# Variable_Load.net
KiCad netlist of a schematic drawn in EAGLE
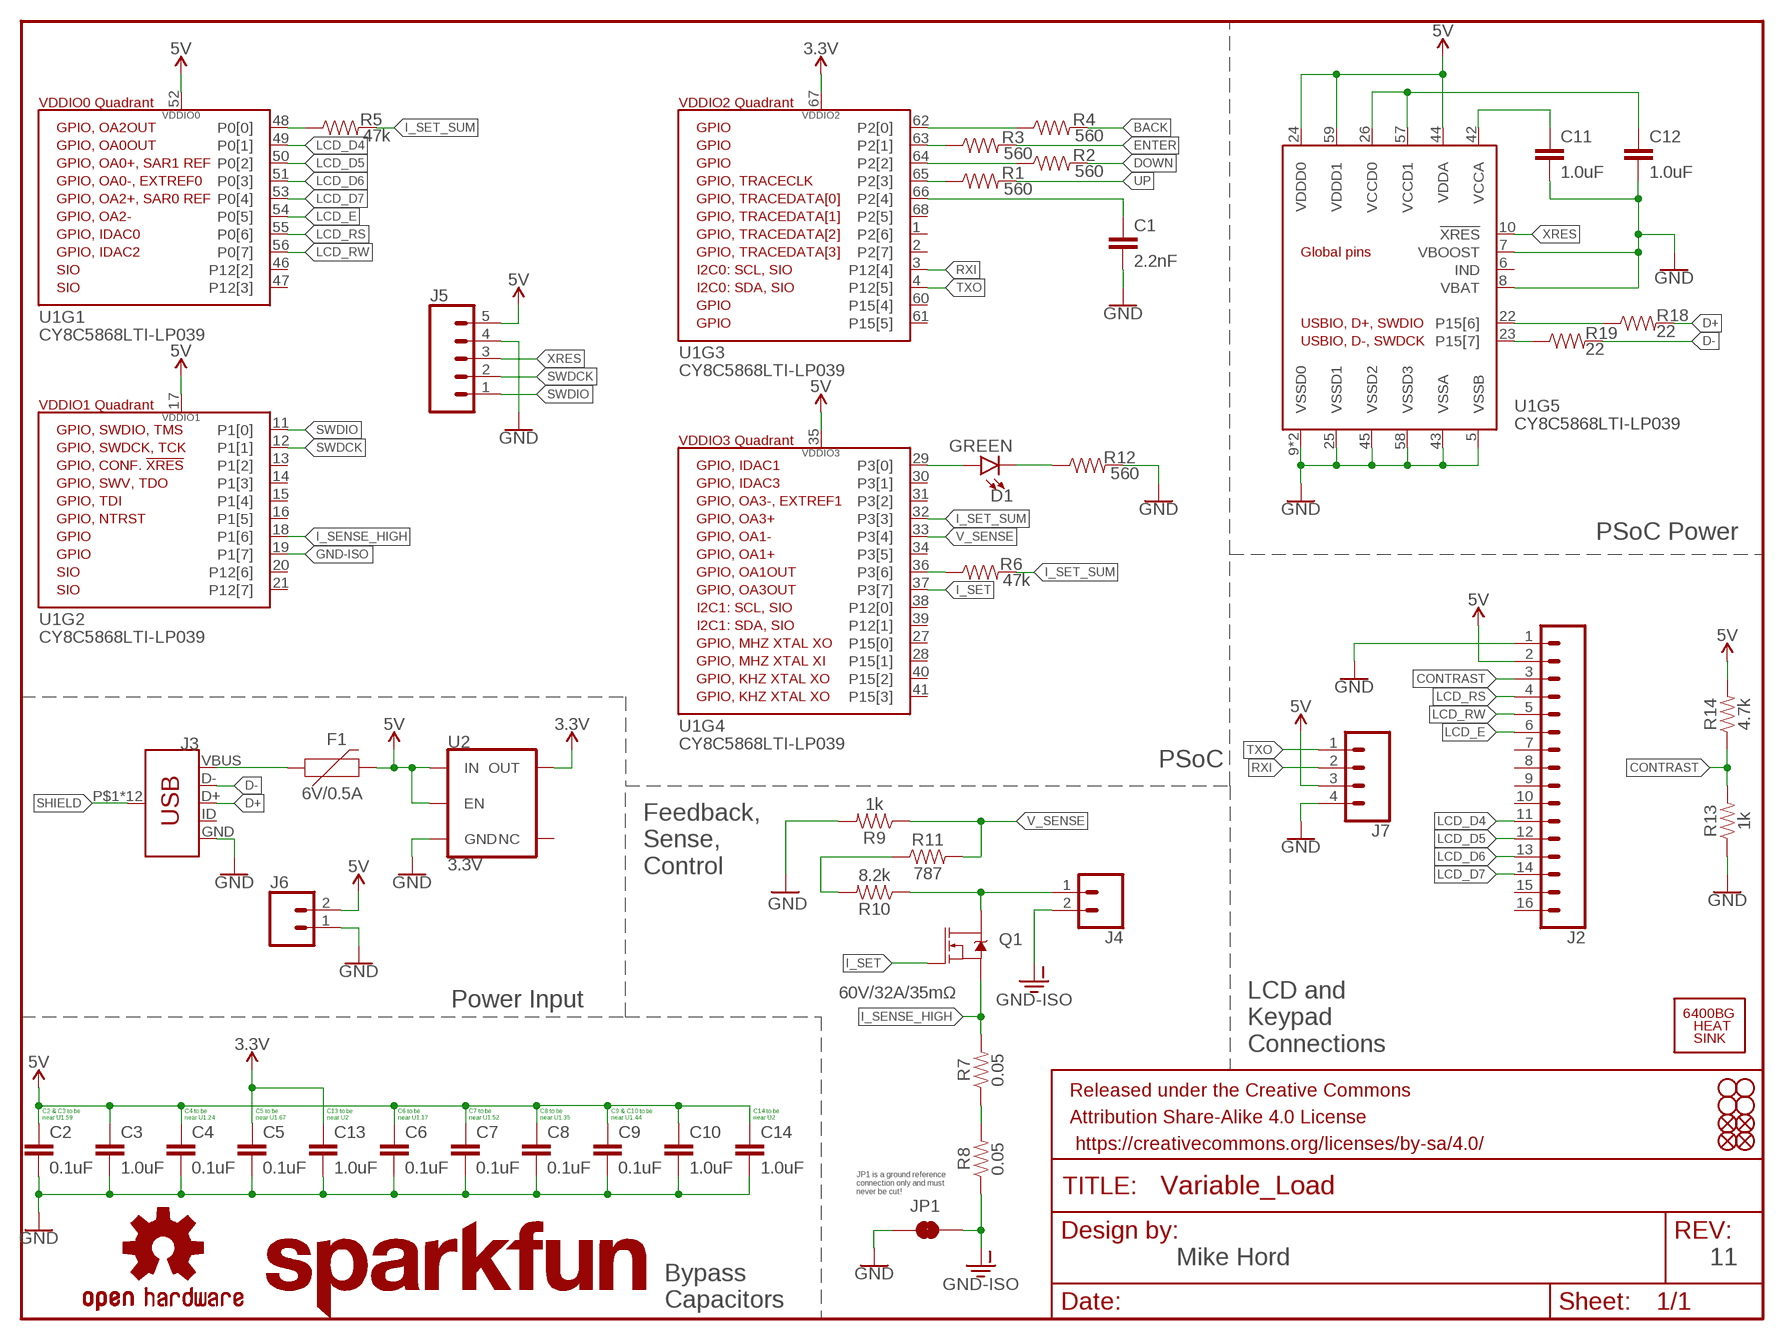
[diagram p0: schematic, sheet 1]

(export (version "E")
  (design (tool "Eeschema 10.0.6"))
  (components
    (comp (ref "C1")
      (value "2.2nF")
      (footprint "eagle-import:0603")
      (libsource (lib "eagle-import") (part "2.2NF/2200PF-0603-50V-10%"))
    )
    (comp (ref "C2")
      (value "0.1uF")
      (footprint "eagle-import:0402")
      (libsource (lib "eagle-import") (part "0.1UF-0402-16V-10%"))
    )
    (comp (ref "C3")
      (value "1.0uF")
      (footprint "eagle-import:0402")
      (libsource (lib "eagle-import") (part "1.0UF-0402-16V-10%"))
    )
    (comp (ref "C4")
      (value "0.1uF")
      (footprint "eagle-import:0402")
      (libsource (lib "eagle-import") (part "0.1UF-0402-16V-10%"))
    )
    (comp (ref "C5")
      (value "0.1uF")
      (footprint "eagle-import:0402")
      (libsource (lib "eagle-import") (part "0.1UF-0402-16V-10%"))
    )
    (comp (ref "C6")
      (value "0.1uF")
      (footprint "eagle-import:0402")
      (libsource (lib "eagle-import") (part "0.1UF-0402-16V-10%"))
    )
    (comp (ref "C7")
      (value "0.1uF")
      (footprint "eagle-import:0402")
      (libsource (lib "eagle-import") (part "0.1UF-0402-16V-10%"))
    )
    (comp (ref "C8")
      (value "0.1uF")
      (footprint "eagle-import:0402")
      (libsource (lib "eagle-import") (part "0.1UF-0402-16V-10%"))
    )
    (comp (ref "C9")
      (value "0.1uF")
      (footprint "eagle-import:0402")
      (libsource (lib "eagle-import") (part "0.1UF-0402-16V-10%"))
    )
    (comp (ref "C10")
      (value "1.0uF")
      (footprint "eagle-import:0402")
      (libsource (lib "eagle-import") (part "1.0UF-0402-16V-10%"))
    )
    (comp (ref "C11")
      (value "1.0uF")
      (footprint "eagle-import:0402")
      (libsource (lib "eagle-import") (part "1.0UF-0402-16V-10%"))
    )
    (comp (ref "C12")
      (value "1.0uF")
      (footprint "eagle-import:0402")
      (libsource (lib "eagle-import") (part "1.0UF-0402-16V-10%"))
    )
    (comp (ref "C13")
      (value "1.0uF")
      (footprint "eagle-import:0402")
      (libsource (lib "eagle-import") (part "1.0UF-0402-16V-10%"))
    )
    (comp (ref "C14")
      (value "1.0uF")
      (footprint "eagle-import:0402")
      (libsource (lib "eagle-import") (part "1.0UF-0402-16V-10%"))
    )
    (comp (ref "D1")
      (value "GREEN")
      (footprint "eagle-import:LED-1206-BOTTOM")
      (libsource (lib "eagle-import") (part "LED1206-BOTTOM"))
    )
    (comp (ref "F1")
      (value "6V/0.5A")
      (footprint "eagle-import:1206")
      (libsource (lib "eagle-import") (part "PPTC_HALF-AMP"))
    )
    (comp (ref "FD1")
      (value "FIDUCIAL1X2")
      (footprint "eagle-import:FIDUCIAL-1X2")
      (libsource (lib "eagle-import") (part "FIDUCIAL1X2"))
    )
    (comp (ref "FD2")
      (value "FIDUCIAL1X2")
      (footprint "eagle-import:FIDUCIAL-1X2")
      (libsource (lib "eagle-import") (part "FIDUCIAL1X2"))
    )
    (comp (ref "FD3")
      (value "FIDUCIAL1X2")
      (footprint "eagle-import:FIDUCIAL-1X2")
      (libsource (lib "eagle-import") (part "FIDUCIAL1X2"))
    )
    (comp (ref "FD4")
      (value "FIDUCIAL1X2")
      (footprint "eagle-import:FIDUCIAL-1X2")
      (libsource (lib "eagle-import") (part "FIDUCIAL1X2"))
    )
    (comp (ref "FRAME1")
      (value "FRAME-LETTER")
      (footprint "eagle-import:CREATIVE_COMMONS")
      (libsource (lib "eagle-import") (part "FRAME-LETTER"))
    )
    (comp (ref "H1")
      (value "6400BG_HEATSINK")
      (footprint "eagle-import:6400BG_HEATSINK")
      (libsource (lib "eagle-import") (part "6400BG_HEATSINK"))
    )
    (comp (ref "H2")
      (value "STAND-OFF")
      (footprint "eagle-import:STAND-OFF")
      (libsource (lib "eagle-import") (part "STAND-OFF"))
    )
    (comp (ref "H3")
      (value "STAND-OFF")
      (footprint "eagle-import:STAND-OFF")
      (libsource (lib "eagle-import") (part "STAND-OFF"))
    )
    (comp (ref "H4")
      (value "STAND-OFF")
      (footprint "eagle-import:STAND-OFF")
      (libsource (lib "eagle-import") (part "STAND-OFF"))
    )
    (comp (ref "H5")
      (value "STAND-OFF")
      (footprint "eagle-import:STAND-OFF")
      (libsource (lib "eagle-import") (part "STAND-OFF"))
    )
    (comp (ref "J2")
      (value "CONN_16")
      (footprint "eagle-import:1X16")
      (libsource (lib "eagle-import") (part "CONN_16"))
    )
    (comp (ref "J3")
      (value "AMP FCI 10103594-0001LF")
      (footprint "eagle-import:USB-MICROB-PTH")
      (libsource (lib "eagle-import") (part "USB_MICRO-B_HALF_PTH"))
    )
    (comp (ref "J4")
      (value "CONN_023.5MM_LOCK")
      (footprint "eagle-import:SCREWTERMINAL-3.5MM-2_LOCK")
      (libsource (lib "eagle-import") (part "CONN_023.5MM_LOCK"))
    )
    (comp (ref "J5")
      (value "CONN_05")
      (footprint "eagle-import:1X05")
      (libsource (lib "eagle-import") (part "CONN_05"))
    )
    (comp (ref "J6")
      (value "CONN_02")
      (footprint "eagle-import:1X02")
      (libsource (lib "eagle-import") (part "CONN_02"))
    )
    (comp (ref "J7")
      (value "CONN_04")
      (footprint "eagle-import:1X04")
      (libsource (lib "eagle-import") (part "CONN_04"))
    )
    (comp (ref "JP1")
      (value "JUMPER-SMT_2_NC_TRACE_NO-SILK")
      (footprint "eagle-import:SMT-JUMPER_2_NC_TRACE_NO-SILK")
      (libsource (lib "eagle-import") (part "JUMPER-SMT_2_NC_TRACE_NO-SILK"))
    )
    (comp (ref "LOGO1")
      (value "OSHW-LOGOM")
      (footprint "eagle-import:OSHW-LOGO-M")
      (libsource (lib "eagle-import") (part "OSHW-LOGOM"))
    )
    (comp (ref "LOGO2")
      (value "SFE_LOGO_NAME.3_INCH")
      (footprint "eagle-import:SFE_LOGO_NAME_.3")
      (libsource (lib "eagle-import") (part "SFE_LOGO_NAME.3_INCH"))
    )
    (comp (ref "LOGO3")
      (value "SFE_LOGO_NAME.3_INCH")
      (footprint "eagle-import:SFE_LOGO_NAME_.3")
      (libsource (lib "eagle-import") (part "SFE_LOGO_NAME.3_INCH"))
    )
    (comp (ref "Q1")
      (value "60V/32A/35mΩ")
      (footprint "eagle-import:TO220V")
      (libsource (lib "eagle-import") (part "MOSFET-NCH-FQP30N06L"))
    )
    (comp (ref "R1")
      (value "560")
      (footprint "eagle-import:0402")
      (libsource (lib "eagle-import") (part "560OHM_0402_1%"))
    )
    (comp (ref "R2")
      (value "560")
      (footprint "eagle-import:0402")
      (libsource (lib "eagle-import") (part "560OHM_0402_1%"))
    )
    (comp (ref "R3")
      (value "560")
      (footprint "eagle-import:0402")
      (libsource (lib "eagle-import") (part "560OHM_0402_1%"))
    )
    (comp (ref "R4")
      (value "560")
      (footprint "eagle-import:0402")
      (libsource (lib "eagle-import") (part "560OHM_0402_1%"))
    )
    (comp (ref "R5")
      (value "47k")
      (footprint "eagle-import:0603")
      (libsource (lib "eagle-import") (part "47KOHM-0603-1/10W-1%"))
    )
    (comp (ref "R6")
      (value "47k")
      (footprint "eagle-import:0603")
      (libsource (lib "eagle-import") (part "47KOHM-0603-1/10W-1%"))
    )
    (comp (ref "R7")
      (value "0.05")
      (footprint "eagle-import:2512")
      (libsource (lib "eagle-import") (part "0.05OHM-2512-3W-1%"))
    )
    (comp (ref "R8")
      (value "0.05")
      (footprint "eagle-import:2512")
      (libsource (lib "eagle-import") (part "0.05OHM-2512-3W-1%"))
    )
    (comp (ref "R9")
      (value "1k")
      (footprint "eagle-import:0603")
      (libsource (lib "eagle-import") (part "1KOHM-0603-1/10W-1%"))
    )
    (comp (ref "R10")
      (value "8.2k")
      (footprint "eagle-import:0603")
      (libsource (lib "eagle-import") (part "8.2KOHM-0603-1/10W-5%"))
    )
    (comp (ref "R11")
      (value "787")
      (footprint "eagle-import:0603")
      (libsource (lib "eagle-import") (part "787OHM-0603-1/10W-1%"))
    )
    (comp (ref "R12")
      (value "560")
      (footprint "eagle-import:0402")
      (libsource (lib "eagle-import") (part "560OHM_0402_1%"))
    )
    (comp (ref "R13")
      (value "1k")
      (footprint "eagle-import:0603")
      (libsource (lib "eagle-import") (part "1KOHM-0603-1/10W-1%"))
    )
    (comp (ref "R14")
      (value "4.7k")
      (footprint "eagle-import:0603")
      (libsource (lib "eagle-import") (part "4.7KOHM-0603-1/10W-1%"))
    )
    (comp (ref "R18")
      (value "22")
      (footprint "eagle-import:0402-RES")
      (libsource (lib "eagle-import") (part "22OHM1/10W1%(0402)"))
    )
    (comp (ref "R19")
      (value "22")
      (footprint "eagle-import:0402-RES")
      (libsource (lib "eagle-import") (part "22OHM1/10W1%(0402)"))
    )
    (comp (ref "U1")
      (value "CY8C5868LTI-LP039")
      (footprint "eagle-import:QFN-68")
      (libsource (lib "eagle-import") (part "PSOC_5LP_68QFN"))
    )
    (comp (ref "U2")
      (value "3.3V")
      (footprint "eagle-import:SOT23-5")
      (libsource (lib "eagle-import") (part "V_REG_AP2112K-3.3V"))
    )
  )
  (nets
    (net (code "1") (name "3.3V") (class "Default")
      (node (ref "C13") (pin "1") (pinfunction "1_1") (pintype "passive"))
      (node (ref "C5") (pin "1") (pinfunction "1_1") (pintype "passive"))
      (node (ref "U1") (pin "67") (pinfunction "VDDIO2_67") (pintype "bidirectional"))
      (node (ref "U2") (pin "5") (pinfunction "OUT_5") (pintype "passive"))
    )
    (net (code "2") (name "5V") (class "Default")
      (node (ref "C10") (pin "1") (pinfunction "1_1") (pintype "passive"))
      (node (ref "C14") (pin "1") (pinfunction "1_1") (pintype "passive"))
      (node (ref "C2") (pin "1") (pinfunction "1_1") (pintype "passive"))
      (node (ref "C3") (pin "1") (pinfunction "1_1") (pintype "passive"))
      (node (ref "C4") (pin "1") (pinfunction "1_1") (pintype "passive"))
      (node (ref "C6") (pin "1") (pinfunction "1_1") (pintype "passive"))
      (node (ref "C7") (pin "1") (pinfunction "1_1") (pintype "passive"))
      (node (ref "C8") (pin "1") (pinfunction "1_1") (pintype "passive"))
      (node (ref "C9") (pin "1") (pinfunction "1_1") (pintype "passive"))
      (node (ref "F1") (pin "2") (pinfunction "2_2") (pintype "bidirectional"))
      (node (ref "J2") (pin "2") (pinfunction "2_2") (pintype "passive"))
      (node (ref "J5") (pin "5") (pinfunction "5_5") (pintype "passive"))
      (node (ref "J6") (pin "2") (pinfunction "2_2") (pintype "passive"))
      (node (ref "J7") (pin "3") (pinfunction "3_3") (pintype "passive"))
      (node (ref "R14") (pin "2") (pinfunction "2_2") (pintype "passive"))
      (node (ref "U1") (pin "17") (pinfunction "VDDIO1_17") (pintype "bidirectional"))
      (node (ref "U1") (pin "24") (pinfunction "VDDD0_24") (pintype "bidirectional"))
      (node (ref "U1") (pin "35") (pinfunction "VDDIO3_35") (pintype "bidirectional"))
      (node (ref "U1") (pin "44") (pinfunction "VDDA_44") (pintype "bidirectional"))
      (node (ref "U1") (pin "52") (pinfunction "VDDIO0_52") (pintype "bidirectional"))
      (node (ref "U1") (pin "59") (pinfunction "VDDD1_59") (pintype "bidirectional"))
      (node (ref "U2") (pin "1") (pinfunction "IN_1") (pintype "input"))
      (node (ref "U2") (pin "3") (pinfunction "EN_3") (pintype "input"))
    )
    (net (code "3") (name "BACK") (class "Default")
      (node (ref "R4") (pin "2") (pinfunction "2_2") (pintype "passive"))
    )
    (net (code "4") (name "CONTRAST") (class "Default")
      (node (ref "J2") (pin "3") (pinfunction "3_3") (pintype "passive"))
      (node (ref "R13") (pin "2") (pinfunction "2_2") (pintype "passive"))
      (node (ref "R14") (pin "1") (pinfunction "1_1") (pintype "passive"))
    )
    (net (code "5") (name "D+") (class "Default")
      (node (ref "J3") (pin "D+") (pinfunction "D+_D+") (pintype "bidirectional"))
      (node (ref "R18") (pin "2") (pinfunction "2_2") (pintype "passive"))
    )
    (net (code "6") (name "D-") (class "Default")
      (node (ref "J3") (pin "D-") (pinfunction "D-_D-") (pintype "bidirectional"))
      (node (ref "R19") (pin "2") (pinfunction "2_2") (pintype "passive"))
    )
    (net (code "7") (name "DOWN") (class "Default")
      (node (ref "R2") (pin "2") (pinfunction "2_2") (pintype "passive"))
    )
    (net (code "8") (name "ENTER") (class "Default")
      (node (ref "R3") (pin "2") (pinfunction "2_2") (pintype "passive"))
    )
    (net (code "9") (name "GND") (class "Default")
      (node (ref "C1") (pin "2") (pinfunction "2_2") (pintype "passive"))
      (node (ref "C10") (pin "2") (pinfunction "2_2") (pintype "passive"))
      (node (ref "C11") (pin "2") (pinfunction "2_2") (pintype "passive"))
      (node (ref "C12") (pin "2") (pinfunction "2_2") (pintype "passive"))
      (node (ref "C13") (pin "2") (pinfunction "2_2") (pintype "passive"))
      (node (ref "C14") (pin "2") (pinfunction "2_2") (pintype "passive"))
      (node (ref "C2") (pin "2") (pinfunction "2_2") (pintype "passive"))
      (node (ref "C3") (pin "2") (pinfunction "2_2") (pintype "passive"))
      (node (ref "C4") (pin "2") (pinfunction "2_2") (pintype "passive"))
      (node (ref "C5") (pin "2") (pinfunction "2_2") (pintype "passive"))
      (node (ref "C6") (pin "2") (pinfunction "2_2") (pintype "passive"))
      (node (ref "C7") (pin "2") (pinfunction "2_2") (pintype "passive"))
      (node (ref "C8") (pin "2") (pinfunction "2_2") (pintype "passive"))
      (node (ref "C9") (pin "2") (pinfunction "2_2") (pintype "passive"))
      (node (ref "J2") (pin "1") (pinfunction "1_1") (pintype "passive"))
      (node (ref "J3") (pin "GND") (pinfunction "GND_GND") (pintype "power_in"))
      (node (ref "J5") (pin "4") (pinfunction "4_4") (pintype "passive"))
      (node (ref "J6") (pin "1") (pinfunction "1_1") (pintype "passive"))
      (node (ref "J7") (pin "4") (pinfunction "4_4") (pintype "passive"))
      (node (ref "JP1") (pin "1") (pinfunction "1_1") (pintype "passive"))
      (node (ref "R12") (pin "2") (pinfunction "2_2") (pintype "passive"))
      (node (ref "R13") (pin "1") (pinfunction "1_1") (pintype "passive"))
      (node (ref "R9") (pin "2") (pinfunction "2_2") (pintype "passive"))
      (node (ref "U1") (pin "25") (pinfunction "VSSD1_25") (pintype "bidirectional"))
      (node (ref "U1") (pin "43") (pinfunction "VSSA_43") (pintype "bidirectional"))
      (node (ref "U1") (pin "45") (pinfunction "VSSD2_45") (pintype "bidirectional"))
      (node (ref "U1") (pin "5") (pinfunction "VSSB_5") (pintype "bidirectional"))
      (node (ref "U1") (pin "58") (pinfunction "VSSD3_58") (pintype "bidirectional"))
      (node (ref "U1") (pin "69") (pinfunction "VSSD0_69") (pintype "bidirectional"))
      (node (ref "U1") (pin "7") (pinfunction "VBOOST_7") (pintype "bidirectional"))
      (node (ref "U1") (pin "8") (pinfunction "VBAT_8") (pintype "bidirectional"))
      (node (ref "U1") (pin "9") (pinfunction "VSSD0_9") (pintype "bidirectional"))
      (node (ref "U2") (pin "2") (pinfunction "GND_2") (pintype "input"))
    )
    (net (code "10") (name "GND-ISO") (class "Default")
      (node (ref "J4") (pin "2") (pinfunction "2_2") (pintype "passive"))
      (node (ref "JP1") (pin "2") (pinfunction "2_2") (pintype "passive"))
      (node (ref "R8") (pin "P$1") (pinfunction "1_P$1") (pintype "passive"))
      (node (ref "U1") (pin "19") (pinfunction "P1[7]_19") (pintype "bidirectional"))
    )
    (net (code "11") (name "I_SENSE_HIGH") (class "Default")
      (node (ref "Q1") (pin "3") (pinfunction "S_3") (pintype "bidirectional"))
      (node (ref "R7") (pin "P$2") (pinfunction "2_P$2") (pintype "passive"))
      (node (ref "U1") (pin "18") (pinfunction "P1[6]_18") (pintype "bidirectional"))
    )
    (net (code "12") (name "I_SET") (class "Default")
      (node (ref "Q1") (pin "1") (pinfunction "G_1") (pintype "bidirectional"))
      (node (ref "U1") (pin "37") (pinfunction "P3[7]_37") (pintype "bidirectional"))
    )
    (net (code "13") (name "I_SET_SUM") (class "Default")
      (node (ref "R5") (pin "2") (pinfunction "2_2") (pintype "passive"))
      (node (ref "R6") (pin "2") (pinfunction "2_2") (pintype "passive"))
      (node (ref "U1") (pin "32") (pinfunction "P3[3]_32") (pintype "bidirectional"))
    )
    (net (code "14") (name "LCD_D4") (class "Default")
      (node (ref "J2") (pin "11") (pinfunction "11_11") (pintype "passive"))
      (node (ref "U1") (pin "49") (pinfunction "P0[1]_49") (pintype "bidirectional"))
    )
    (net (code "15") (name "LCD_D5") (class "Default")
      (node (ref "J2") (pin "12") (pinfunction "12_12") (pintype "passive"))
      (node (ref "U1") (pin "50") (pinfunction "P0[2]_50") (pintype "bidirectional"))
    )
    (net (code "16") (name "LCD_D6") (class "Default")
      (node (ref "J2") (pin "13") (pinfunction "13_13") (pintype "passive"))
      (node (ref "U1") (pin "51") (pinfunction "P0[3]_51") (pintype "bidirectional"))
    )
    (net (code "17") (name "LCD_D7") (class "Default")
      (node (ref "J2") (pin "14") (pinfunction "14_14") (pintype "passive"))
      (node (ref "U1") (pin "53") (pinfunction "P0[4]_53") (pintype "bidirectional"))
    )
    (net (code "18") (name "LCD_E") (class "Default")
      (node (ref "J2") (pin "6") (pinfunction "6_6") (pintype "passive"))
      (node (ref "U1") (pin "54") (pinfunction "P0[5]_54") (pintype "bidirectional"))
    )
    (net (code "19") (name "LCD_RS") (class "Default")
      (node (ref "J2") (pin "4") (pinfunction "4_4") (pintype "passive"))
      (node (ref "U1") (pin "55") (pinfunction "P0[6]_55") (pintype "bidirectional"))
    )
    (net (code "20") (name "LCD_RW") (class "Default")
      (node (ref "J2") (pin "5") (pinfunction "5_5") (pintype "passive"))
      (node (ref "U1") (pin "56") (pinfunction "P0[7]_56") (pintype "bidirectional"))
    )
    (net (code "21") (name "Net-(D1-PadC)") (class "Default")
      (node (ref "D1") (pin "C") (pinfunction "C_C") (pintype "passive"))
      (node (ref "R12") (pin "1") (pinfunction "1_1") (pintype "passive"))
    )
    (net (code "22") (name "Net-(F1-Pad1)") (class "Default")
      (node (ref "F1") (pin "1") (pinfunction "1_1") (pintype "bidirectional"))
      (node (ref "J3") (pin "VBUS") (pinfunction "VBUS_VBUS") (pintype "power_in"))
    )
    (net (code "23") (name "Net-(Q1-D)") (class "Default")
      (node (ref "J4") (pin "1") (pinfunction "1_1") (pintype "passive"))
      (node (ref "Q1") (pin "2") (pinfunction "D_2") (pintype "bidirectional"))
      (node (ref "R10") (pin "1") (pinfunction "1_1") (pintype "passive"))
    )
    (net (code "24") (name "Net-(R7-1)") (class "Default")
      (node (ref "R7") (pin "P$1") (pinfunction "1_P$1") (pintype "passive"))
      (node (ref "R8") (pin "P$2") (pinfunction "2_P$2") (pintype "passive"))
    )
    (net (code "25") (name "Net-(R10-Pad2)") (class "Default")
      (node (ref "R10") (pin "2") (pinfunction "2_2") (pintype "passive"))
      (node (ref "R11") (pin "1") (pinfunction "1_1") (pintype "passive"))
    )
    (net (code "26") (name "Net-(U1A-P0[0])") (class "Default")
      (node (ref "R5") (pin "1") (pinfunction "1_1") (pintype "passive"))
      (node (ref "U1") (pin "48") (pinfunction "P0[0]_48") (pintype "bidirectional"))
    )
    (net (code "27") (name "Net-(U1C-P2[0])") (class "Default")
      (node (ref "R4") (pin "1") (pinfunction "1_1") (pintype "passive"))
      (node (ref "U1") (pin "62") (pinfunction "P2[0]_62") (pintype "bidirectional"))
    )
    (net (code "28") (name "Net-(U1C-P2[1])") (class "Default")
      (node (ref "R3") (pin "1") (pinfunction "1_1") (pintype "passive"))
      (node (ref "U1") (pin "63") (pinfunction "P2[1]_63") (pintype "bidirectional"))
    )
    (net (code "29") (name "Net-(U1C-P2[2])") (class "Default")
      (node (ref "R2") (pin "1") (pinfunction "1_1") (pintype "passive"))
      (node (ref "U1") (pin "64") (pinfunction "P2[2]_64") (pintype "bidirectional"))
    )
    (net (code "30") (name "Net-(U1C-P2[3])") (class "Default")
      (node (ref "R1") (pin "1") (pinfunction "1_1") (pintype "passive"))
      (node (ref "U1") (pin "65") (pinfunction "P2[3]_65") (pintype "bidirectional"))
    )
    (net (code "31") (name "Net-(U1C-P2[4])") (class "Default")
      (node (ref "C1") (pin "1") (pinfunction "1_1") (pintype "passive"))
      (node (ref "U1") (pin "66") (pinfunction "P2[4]_66") (pintype "bidirectional"))
    )
    (net (code "32") (name "Net-(U1D-P3[0])") (class "Default")
      (node (ref "D1") (pin "A") (pinfunction "A_A") (pintype "passive"))
      (node (ref "U1") (pin "29") (pinfunction "P3[0]_29") (pintype "bidirectional"))
    )
    (net (code "33") (name "Net-(U1D-P3[6])") (class "Default")
      (node (ref "R6") (pin "1") (pinfunction "1_1") (pintype "passive"))
      (node (ref "U1") (pin "36") (pinfunction "P3[6]_36") (pintype "bidirectional"))
    )
    (net (code "34") (name "Net-(U1E-P15[6])") (class "Default")
      (node (ref "R18") (pin "1") (pinfunction "1_1") (pintype "passive"))
      (node (ref "U1") (pin "22") (pinfunction "P15[6]_22") (pintype "bidirectional"))
    )
    (net (code "35") (name "Net-(U1E-P15[7])") (class "Default")
      (node (ref "R19") (pin "1") (pinfunction "1_1") (pintype "passive"))
      (node (ref "U1") (pin "23") (pinfunction "P15[7]_23") (pintype "bidirectional"))
    )
    (net (code "36") (name "Net-(U1E-VCCA)") (class "Default")
      (node (ref "C11") (pin "1") (pinfunction "1_1") (pintype "passive"))
      (node (ref "U1") (pin "42") (pinfunction "VCCA_42") (pintype "bidirectional"))
    )
    (net (code "37") (name "Net-(U1E-VCCD0)") (class "Default")
      (node (ref "C12") (pin "1") (pinfunction "1_1") (pintype "passive"))
      (node (ref "U1") (pin "26") (pinfunction "VCCD0_26") (pintype "bidirectional"))
      (node (ref "U1") (pin "57") (pinfunction "VCCD1_57") (pintype "bidirectional"))
    )
    (net (code "38") (name "RXI") (class "Default")
      (node (ref "J7") (pin "2") (pinfunction "2_2") (pintype "passive"))
      (node (ref "U1") (pin "3") (pinfunction "P12[4]_3") (pintype "bidirectional"))
    )
    (net (code "39") (name "SHIELD") (class "Default")
      (node (ref "J3") (pin "P$1") (pinfunction "SHIELD_P$1") (pintype "bidirectional"))
      (node (ref "J3") (pin "P$10") (pinfunction "SHIELD_P$10") (pintype "bidirectional"))
      (node (ref "J3") (pin "P$12") (pinfunction "SHIELD_P$12") (pintype "bidirectional"))
      (node (ref "J3") (pin "P$2") (pinfunction "SHIELD_P$2") (pintype "bidirectional"))
      (node (ref "J3") (pin "P$3") (pinfunction "SHIELD_P$3") (pintype "bidirectional"))
      (node (ref "J3") (pin "P$4") (pinfunction "SHIELD_P$4") (pintype "bidirectional"))
      (node (ref "J3") (pin "P$6") (pinfunction "SHIELD_P$6") (pintype "bidirectional"))
      (node (ref "J3") (pin "P$8") (pinfunction "SHIELD_P$8") (pintype "bidirectional"))
      (node (ref "J3") (pin "SHEILD2") (pinfunction "SHIELD_SHEILD2") (pintype "bidirectional"))
      (node (ref "J3") (pin "SHIELD") (pinfunction "SHIELD_SHIELD") (pintype "bidirectional"))
      (node (ref "J3") (pin "SHIELD3") (pinfunction "SHIELD_SHIELD3") (pintype "bidirectional"))
      (node (ref "J3") (pin "SHIELD4") (pinfunction "SHIELD_SHIELD4") (pintype "bidirectional"))
    )
    (net (code "40") (name "SWDCK") (class "Default")
      (node (ref "J5") (pin "2") (pinfunction "2_2") (pintype "passive"))
      (node (ref "U1") (pin "12") (pinfunction "P1[1]_12") (pintype "bidirectional"))
    )
    (net (code "41") (name "SWDIO") (class "Default")
      (node (ref "J5") (pin "1") (pinfunction "1_1") (pintype "passive"))
      (node (ref "U1") (pin "11") (pinfunction "P1[0]_11") (pintype "bidirectional"))
    )
    (net (code "42") (name "TXO") (class "Default")
      (node (ref "J7") (pin "1") (pinfunction "1_1") (pintype "passive"))
      (node (ref "U1") (pin "4") (pinfunction "P12[5]_4") (pintype "bidirectional"))
    )
    (net (code "43") (name "UP") (class "Default")
      (node (ref "R1") (pin "2") (pinfunction "2_2") (pintype "passive"))
    )
    (net (code "44") (name "V_SENSE") (class "Default")
      (node (ref "R11") (pin "2") (pinfunction "2_2") (pintype "passive"))
      (node (ref "R9") (pin "1") (pinfunction "1_1") (pintype "passive"))
      (node (ref "U1") (pin "33") (pinfunction "P3[4]_33") (pintype "bidirectional"))
    )
    (net (code "45") (name "XRES") (class "Default")
      (node (ref "J5") (pin "3") (pinfunction "3_3") (pintype "passive"))
      (node (ref "U1") (pin "10") (pinfunction "~{XRES}_10") (pintype "bidirectional"))
    )
    (net (code "46") (name "unconnected-(J2-Pad7)") (class "Default")
      (node (ref "J2") (pin "7") (pinfunction "7_7") (pintype "passive"))
    )
    (net (code "47") (name "unconnected-(J2-Pad8)") (class "Default")
      (node (ref "J2") (pin "8") (pinfunction "8_8") (pintype "passive"))
    )
    (net (code "48") (name "unconnected-(J2-Pad9)") (class "Default")
      (node (ref "J2") (pin "9") (pinfunction "9_9") (pintype "passive"))
    )
    (net (code "49") (name "unconnected-(J2-Pad10)") (class "Default")
      (node (ref "J2") (pin "10") (pinfunction "10_10") (pintype "passive"))
    )
    (net (code "50") (name "unconnected-(J2-Pad15)") (class "Default")
      (node (ref "J2") (pin "15") (pinfunction "15_15") (pintype "passive"))
    )
    (net (code "51") (name "unconnected-(J2-Pad16)") (class "Default")
      (node (ref "J2") (pin "16") (pinfunction "16_16") (pintype "passive"))
    )
    (net (code "52") (name "unconnected-(J3-PadID)") (class "Default")
      (node (ref "J3") (pin "ID") (pinfunction "ID_ID") (pintype "bidirectional"))
    )
    (net (code "53") (name "unconnected-(U1A-P12[2]-Pad46)") (class "Default")
      (node (ref "U1") (pin "46") (pinfunction "P12[2]_46") (pintype "bidirectional"))
    )
    (net (code "54") (name "unconnected-(U1A-P12[3]-Pad47)") (class "Default")
      (node (ref "U1") (pin "47") (pinfunction "P12[3]_47") (pintype "bidirectional"))
    )
    (net (code "55") (name "unconnected-(U1B-P1[2]-Pad13)") (class "Default")
      (node (ref "U1") (pin "13") (pinfunction "P1[2]_13") (pintype "bidirectional"))
    )
    (net (code "56") (name "unconnected-(U1B-P1[3]-Pad14)") (class "Default")
      (node (ref "U1") (pin "14") (pinfunction "P1[3]_14") (pintype "bidirectional"))
    )
    (net (code "57") (name "unconnected-(U1B-P1[4]-Pad15)") (class "Default")
      (node (ref "U1") (pin "15") (pinfunction "P1[4]_15") (pintype "bidirectional"))
    )
    (net (code "58") (name "unconnected-(U1B-P1[5]-Pad16)") (class "Default")
      (node (ref "U1") (pin "16") (pinfunction "P1[5]_16") (pintype "bidirectional"))
    )
    (net (code "59") (name "unconnected-(U1B-P12[6]-Pad20)") (class "Default")
      (node (ref "U1") (pin "20") (pinfunction "P12[6]_20") (pintype "bidirectional"))
    )
    (net (code "60") (name "unconnected-(U1B-P12[7]-Pad21)") (class "Default")
      (node (ref "U1") (pin "21") (pinfunction "P12[7]_21") (pintype "bidirectional"))
    )
    (net (code "61") (name "unconnected-(U1C-P2[5]-Pad68)") (class "Default")
      (node (ref "U1") (pin "68") (pinfunction "P2[5]_68") (pintype "bidirectional"))
    )
    (net (code "62") (name "unconnected-(U1C-P2[6]-Pad1)") (class "Default")
      (node (ref "U1") (pin "1") (pinfunction "P2[6]_1") (pintype "bidirectional"))
    )
    (net (code "63") (name "unconnected-(U1C-P2[7]-Pad2)") (class "Default")
      (node (ref "U1") (pin "2") (pinfunction "P2[7]_2") (pintype "bidirectional"))
    )
    (net (code "64") (name "unconnected-(U1C-P15[4]-Pad60)") (class "Default")
      (node (ref "U1") (pin "60") (pinfunction "P15[4]_60") (pintype "bidirectional"))
    )
    (net (code "65") (name "unconnected-(U1C-P15[5]-Pad61)") (class "Default")
      (node (ref "U1") (pin "61") (pinfunction "P15[5]_61") (pintype "bidirectional"))
    )
    (net (code "66") (name "unconnected-(U1D-P3[1]-Pad30)") (class "Default")
      (node (ref "U1") (pin "30") (pinfunction "P3[1]_30") (pintype "bidirectional"))
    )
    (net (code "67") (name "unconnected-(U1D-P3[2]-Pad31)") (class "Default")
      (node (ref "U1") (pin "31") (pinfunction "P3[2]_31") (pintype "bidirectional"))
    )
    (net (code "68") (name "unconnected-(U1D-P3[5]-Pad34)") (class "Default")
      (node (ref "U1") (pin "34") (pinfunction "P3[5]_34") (pintype "bidirectional"))
    )
    (net (code "69") (name "unconnected-(U1D-P12[0]-Pad38)") (class "Default")
      (node (ref "U1") (pin "38") (pinfunction "P12[0]_38") (pintype "bidirectional"))
    )
    (net (code "70") (name "unconnected-(U1D-P12[1]-Pad39)") (class "Default")
      (node (ref "U1") (pin "39") (pinfunction "P12[1]_39") (pintype "bidirectional"))
    )
    (net (code "71") (name "unconnected-(U1D-P15[0]-Pad27)") (class "Default")
      (node (ref "U1") (pin "27") (pinfunction "P15[0]_27") (pintype "bidirectional"))
    )
    (net (code "72") (name "unconnected-(U1D-P15[1]-Pad28)") (class "Default")
      (node (ref "U1") (pin "28") (pinfunction "P15[1]_28") (pintype "bidirectional"))
    )
    (net (code "73") (name "unconnected-(U1D-P15[2]-Pad40)") (class "Default")
      (node (ref "U1") (pin "40") (pinfunction "P15[2]_40") (pintype "bidirectional"))
    )
    (net (code "74") (name "unconnected-(U1D-P15[3]-Pad41)") (class "Default")
      (node (ref "U1") (pin "41") (pinfunction "P15[3]_41") (pintype "bidirectional"))
    )
    (net (code "75") (name "unconnected-(U1E-IND-Pad6)") (class "Default")
      (node (ref "U1") (pin "6") (pinfunction "IND_6") (pintype "bidirectional"))
    )
    (net (code "76") (name "unconnected-(U2-NC-Pad4)") (class "Default")
      (node (ref "U2") (pin "4") (pinfunction "NC_4") (pintype "no_connect"))
    )
  )
)
